# Bus_IO_and_Centronics_Card.net
KiCad netlist of a schematic drawn in EAGLE
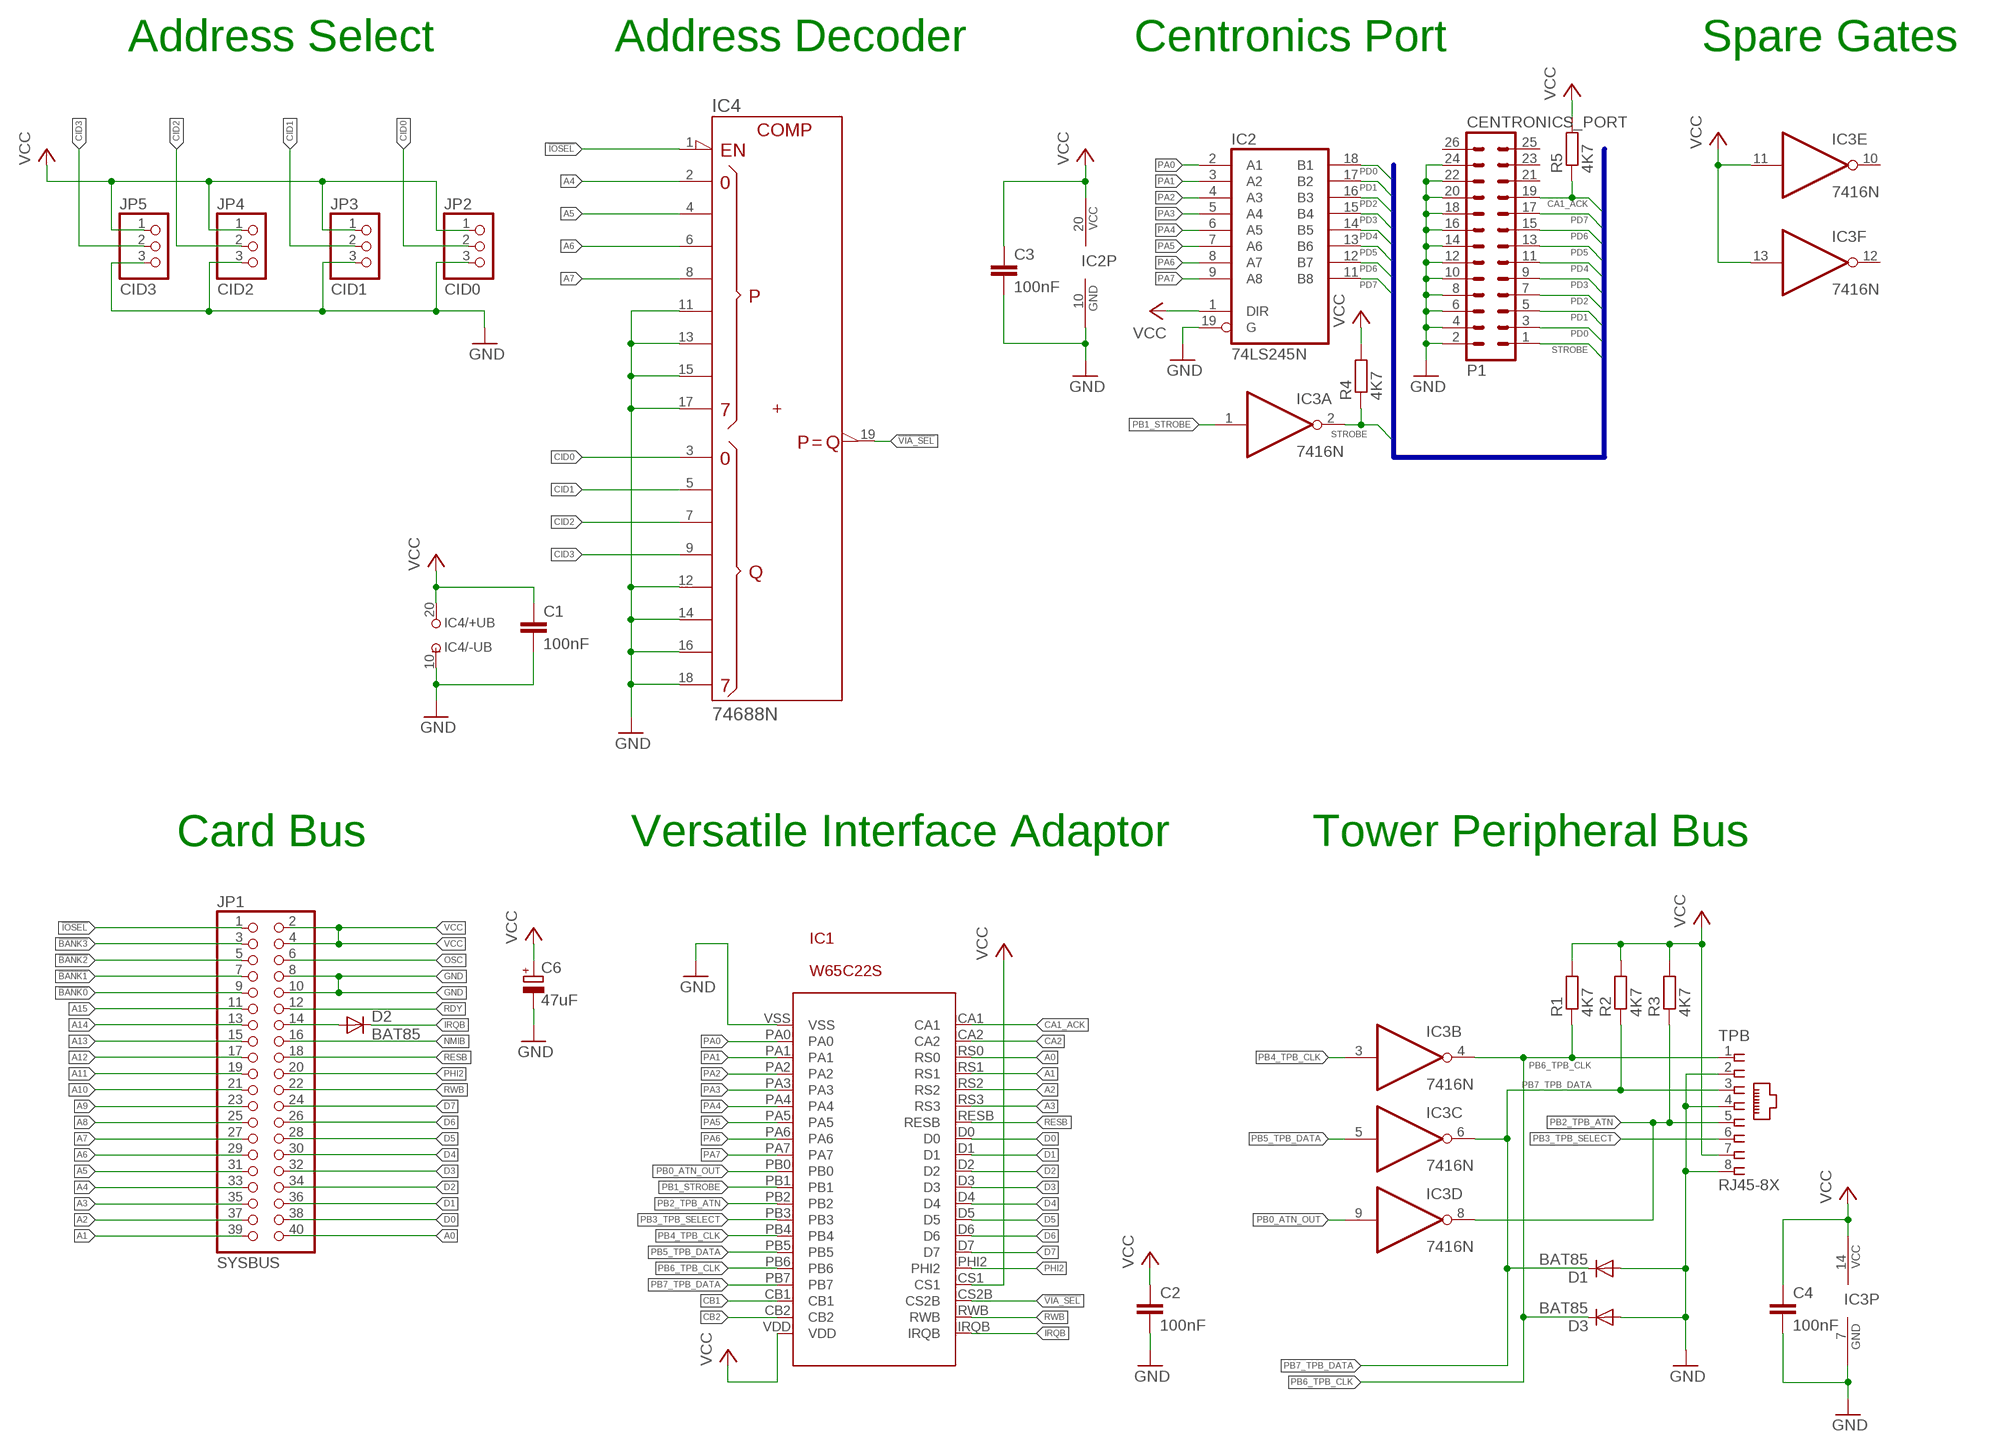
[diagram p0: schematic, sheet 1]

(export (version "E")
  (design (tool "Eeschema 10.0.6"))
  (components
    (comp (ref "C1")
      (value "100nF")
      (footprint "eagle-import:C050-025X075")
      (libsource (lib "eagle-import") (part "C-EU050-025X075"))
    )
    (comp (ref "C2")
      (value "100nF")
      (footprint "eagle-import:C050-025X075")
      (libsource (lib "eagle-import") (part "C-EU050-025X075"))
    )
    (comp (ref "C3")
      (value "100nF")
      (footprint "eagle-import:C050-025X075")
      (libsource (lib "eagle-import") (part "C-EU050-025X075"))
    )
    (comp (ref "C4")
      (value "100nF")
      (footprint "eagle-import:C050-025X075")
      (libsource (lib "eagle-import") (part "C-EU050-025X075"))
    )
    (comp (ref "C6")
      (value "47uF")
      (footprint "eagle-import:E2,5-7")
      (libsource (lib "eagle-import") (part "CPOL-EUE2.5-7"))
    )
    (comp (ref "CENTRONICS_PORT")
      (value "P1")
      (footprint "eagle-import:ML26L")
      (libsource (lib "eagle-import") (part "ML26L"))
    )
    (comp (ref "D1")
      (value "BAT85")
      (footprint "eagle-import:DO34-7")
      (libsource (lib "eagle-import") (part "BAT81"))
    )
    (comp (ref "D2")
      (value "BAT85")
      (footprint "eagle-import:DO34-7")
      (libsource (lib "eagle-import") (part "BAT81"))
    )
    (comp (ref "D3")
      (value "BAT85")
      (footprint "eagle-import:DO34-7")
      (libsource (lib "eagle-import") (part "BAT81"))
    )
    (comp (ref "IC1")
      (value "W65C22S")
      (footprint "eagle-import:W65C22-DIP")
      (libsource (lib "eagle-import") (part "W65C22"))
    )
    (comp (ref "IC2")
      (value "74LS245N")
      (footprint "eagle-import:DIL20")
      (libsource (lib "eagle-import") (part "74245NLS"))
    )
    (comp (ref "IC3")
      (value "7416N")
      (footprint "eagle-import:DIL14")
      (libsource (lib "eagle-import") (part "7416N"))
    )
    (comp (ref "IC4")
      (value "74688N")
      (footprint "eagle-import:DIL20")
      (libsource (lib "eagle-import") (part "74688N"))
    )
    (comp (ref "JP1")
      (value "SYSBUS")
      (footprint "eagle-import:2X20_90")
      (libsource (lib "eagle-import") (part "PINHD-2X20/90"))
    )
    (comp (ref "JP2")
      (value "CID0")
      (footprint "eagle-import:1X03")
      (libsource (lib "eagle-import") (part "PINHD-1X3"))
    )
    (comp (ref "JP3")
      (value "CID1")
      (footprint "eagle-import:1X03")
      (libsource (lib "eagle-import") (part "PINHD-1X3"))
    )
    (comp (ref "JP4")
      (value "CID2")
      (footprint "eagle-import:1X03")
      (libsource (lib "eagle-import") (part "PINHD-1X3"))
    )
    (comp (ref "JP5")
      (value "CID3")
      (footprint "eagle-import:1X03")
      (libsource (lib "eagle-import") (part "PINHD-1X3"))
    )
    (comp (ref "R1")
      (value "4K7")
      (footprint "eagle-import:0207_10")
      (libsource (lib "eagle-import") (part "R-EU_0207/10"))
    )
    (comp (ref "R2")
      (value "4K7")
      (footprint "eagle-import:0207_10")
      (libsource (lib "eagle-import") (part "R-EU_0207/10"))
    )
    (comp (ref "R3")
      (value "4K7")
      (footprint "eagle-import:0207_10")
      (libsource (lib "eagle-import") (part "R-EU_0207/10"))
    )
    (comp (ref "R4")
      (value "4K7")
      (footprint "eagle-import:0207_10")
      (libsource (lib "eagle-import") (part "R-EU_0207/10"))
    )
    (comp (ref "R5")
      (value "4K7")
      (footprint "eagle-import:0207_10")
      (libsource (lib "eagle-import") (part "R-EU_0207/10"))
    )
    (comp (ref "TPB")
      (value "RJ45-8X")
      (footprint "eagle-import:RJ45-NO-SHIELD")
      (libsource (lib "eagle-import") (part "RJ45-8X"))
    )
  )
  (nets
    (net (code "1") (name "/PD0") (class "Default")
      (node (ref "CENTRONICS_PORT") (pin "3") (pinfunction "3_3") (pintype "passive"))
      (node (ref "IC2") (pin "18") (pinfunction "B1_18") (pintype "bidirectional"))
    )
    (net (code "2") (name "/PD1") (class "Default")
      (node (ref "CENTRONICS_PORT") (pin "5") (pinfunction "5_5") (pintype "passive"))
      (node (ref "IC2") (pin "17") (pinfunction "B2_17") (pintype "bidirectional"))
    )
    (net (code "3") (name "/PD2") (class "Default")
      (node (ref "CENTRONICS_PORT") (pin "7") (pinfunction "7_7") (pintype "passive"))
      (node (ref "IC2") (pin "16") (pinfunction "B3_16") (pintype "bidirectional"))
    )
    (net (code "4") (name "/PD3") (class "Default")
      (node (ref "CENTRONICS_PORT") (pin "9") (pinfunction "9_9") (pintype "passive"))
      (node (ref "IC2") (pin "15") (pinfunction "B4_15") (pintype "bidirectional"))
    )
    (net (code "5") (name "/PD4") (class "Default")
      (node (ref "CENTRONICS_PORT") (pin "11") (pinfunction "11_11") (pintype "passive"))
      (node (ref "IC2") (pin "14") (pinfunction "B5_14") (pintype "bidirectional"))
    )
    (net (code "6") (name "/PD5") (class "Default")
      (node (ref "CENTRONICS_PORT") (pin "13") (pinfunction "13_13") (pintype "passive"))
      (node (ref "IC2") (pin "13") (pinfunction "B6_13") (pintype "bidirectional"))
    )
    (net (code "7") (name "/PD6") (class "Default")
      (node (ref "CENTRONICS_PORT") (pin "15") (pinfunction "15_15") (pintype "passive"))
      (node (ref "IC2") (pin "12") (pinfunction "B7_12") (pintype "bidirectional"))
    )
    (net (code "8") (name "/PD7") (class "Default")
      (node (ref "CENTRONICS_PORT") (pin "17") (pinfunction "17_17") (pintype "passive"))
      (node (ref "IC2") (pin "11") (pinfunction "B8_11") (pintype "bidirectional"))
    )
    (net (code "9") (name "/STROBE") (class "Default")
      (node (ref "CENTRONICS_PORT") (pin "1") (pinfunction "1_1") (pintype "passive"))
      (node (ref "IC3") (pin "2") (pinfunction "O_2") (pintype "open_collector"))
      (node (ref "R4") (pin "1") (pinfunction "1_1") (pintype "passive"))
    )
    (net (code "10") (name "/~{BANK0}") (class "Default")
      (node (ref "JP1") (pin "9") (pinfunction "9_9") (pintype "passive"))
    )
    (net (code "11") (name "/~{BANK1}") (class "Default")
      (node (ref "JP1") (pin "7") (pinfunction "7_7") (pintype "passive"))
    )
    (net (code "12") (name "/~{BANK2}") (class "Default")
      (node (ref "JP1") (pin "5") (pinfunction "5_5") (pintype "passive"))
    )
    (net (code "13") (name "/~{BANK3}") (class "Default")
      (node (ref "JP1") (pin "3") (pinfunction "3_3") (pintype "passive"))
    )
    (net (code "14") (name "/~{IOSEL}") (class "Default")
      (node (ref "IC4") (pin "1") (pinfunction "~{G}_1") (pintype "input"))
      (node (ref "JP1") (pin "1") (pinfunction "1_1") (pintype "passive"))
    )
    (net (code "15") (name "/~{VIA_SEL}") (class "Default")
      (node (ref "IC1") (pin "CS2B") (pinfunction "CS2B_CS2B") (pintype "bidirectional"))
      (node (ref "IC4") (pin "19") (pinfunction "~{P=Q}_19") (pintype "output"))
    )
    (net (code "16") (name "A0") (class "Default")
      (node (ref "IC1") (pin "RS0") (pinfunction "RS0_RS0") (pintype "input"))
      (node (ref "JP1") (pin "40") (pinfunction "40_40") (pintype "passive"))
    )
    (net (code "17") (name "A1") (class "Default")
      (node (ref "IC1") (pin "RS1") (pinfunction "RS1_RS1") (pintype "input"))
      (node (ref "JP1") (pin "39") (pinfunction "39_39") (pintype "passive"))
    )
    (net (code "18") (name "A2") (class "Default")
      (node (ref "IC1") (pin "RS2") (pinfunction "RS2_RS2") (pintype "input"))
      (node (ref "JP1") (pin "37") (pinfunction "37_37") (pintype "passive"))
    )
    (net (code "19") (name "A3") (class "Default")
      (node (ref "IC1") (pin "RS3") (pinfunction "RS3_RS3") (pintype "input"))
      (node (ref "JP1") (pin "35") (pinfunction "35_35") (pintype "passive"))
    )
    (net (code "20") (name "A4") (class "Default")
      (node (ref "IC4") (pin "2") (pinfunction "P0_2") (pintype "input"))
      (node (ref "JP1") (pin "33") (pinfunction "33_33") (pintype "passive"))
    )
    (net (code "21") (name "A5") (class "Default")
      (node (ref "IC4") (pin "4") (pinfunction "P1_4") (pintype "input"))
      (node (ref "JP1") (pin "31") (pinfunction "31_31") (pintype "passive"))
    )
    (net (code "22") (name "A6") (class "Default")
      (node (ref "IC4") (pin "6") (pinfunction "P2_6") (pintype "input"))
      (node (ref "JP1") (pin "29") (pinfunction "29_29") (pintype "passive"))
    )
    (net (code "23") (name "A7") (class "Default")
      (node (ref "IC4") (pin "8") (pinfunction "P3_8") (pintype "input"))
      (node (ref "JP1") (pin "27") (pinfunction "27_27") (pintype "passive"))
    )
    (net (code "24") (name "A8") (class "Default")
      (node (ref "JP1") (pin "25") (pinfunction "25_25") (pintype "passive"))
    )
    (net (code "25") (name "A9") (class "Default")
      (node (ref "JP1") (pin "23") (pinfunction "23_23") (pintype "passive"))
    )
    (net (code "26") (name "A10") (class "Default")
      (node (ref "JP1") (pin "21") (pinfunction "21_21") (pintype "passive"))
    )
    (net (code "27") (name "A11") (class "Default")
      (node (ref "JP1") (pin "19") (pinfunction "19_19") (pintype "passive"))
    )
    (net (code "28") (name "A12") (class "Default")
      (node (ref "JP1") (pin "17") (pinfunction "17_17") (pintype "passive"))
    )
    (net (code "29") (name "A13") (class "Default")
      (node (ref "JP1") (pin "15") (pinfunction "15_15") (pintype "passive"))
    )
    (net (code "30") (name "A14") (class "Default")
      (node (ref "JP1") (pin "13") (pinfunction "13_13") (pintype "passive"))
    )
    (net (code "31") (name "A15") (class "Default")
      (node (ref "JP1") (pin "11") (pinfunction "11_11") (pintype "passive"))
    )
    (net (code "32") (name "CA1_ACK") (class "Default")
      (node (ref "CENTRONICS_PORT") (pin "19") (pinfunction "19_19") (pintype "passive"))
      (node (ref "IC1") (pin "CA1") (pinfunction "CA1_CA1") (pintype "bidirectional"))
      (node (ref "R5") (pin "1") (pinfunction "1_1") (pintype "passive"))
    )
    (net (code "33") (name "CA2") (class "Default")
      (node (ref "IC1") (pin "CA2") (pinfunction "CA2_CA2") (pintype "bidirectional"))
    )
    (net (code "34") (name "CB1") (class "Default")
      (node (ref "IC1") (pin "CB1") (pinfunction "CB1_CB1") (pintype "bidirectional"))
    )
    (net (code "35") (name "CB2") (class "Default")
      (node (ref "IC1") (pin "CB2") (pinfunction "CB2_CB2") (pintype "bidirectional"))
    )
    (net (code "36") (name "CID0") (class "Default")
      (node (ref "IC4") (pin "3") (pinfunction "Q0_3") (pintype "input"))
      (node (ref "JP2") (pin "2") (pinfunction "2_2") (pintype "passive"))
    )
    (net (code "37") (name "CID1") (class "Default")
      (node (ref "IC4") (pin "5") (pinfunction "Q1_5") (pintype "input"))
      (node (ref "JP3") (pin "2") (pinfunction "2_2") (pintype "passive"))
    )
    (net (code "38") (name "CID2") (class "Default")
      (node (ref "IC4") (pin "7") (pinfunction "Q2_7") (pintype "input"))
      (node (ref "JP4") (pin "2") (pinfunction "2_2") (pintype "passive"))
    )
    (net (code "39") (name "CID3") (class "Default")
      (node (ref "IC4") (pin "9") (pinfunction "Q3_9") (pintype "input"))
      (node (ref "JP5") (pin "2") (pinfunction "2_2") (pintype "passive"))
    )
    (net (code "40") (name "D0") (class "Default")
      (node (ref "IC1") (pin "D0") (pinfunction "D0_D0") (pintype "bidirectional"))
      (node (ref "JP1") (pin "38") (pinfunction "38_38") (pintype "passive"))
    )
    (net (code "41") (name "D1") (class "Default")
      (node (ref "IC1") (pin "D1") (pinfunction "D1_D1") (pintype "bidirectional"))
      (node (ref "JP1") (pin "36") (pinfunction "36_36") (pintype "passive"))
    )
    (net (code "42") (name "D2") (class "Default")
      (node (ref "IC1") (pin "D2") (pinfunction "D2_D2") (pintype "bidirectional"))
      (node (ref "JP1") (pin "34") (pinfunction "34_34") (pintype "passive"))
    )
    (net (code "43") (name "D3") (class "Default")
      (node (ref "IC1") (pin "D3") (pinfunction "D3_D3") (pintype "bidirectional"))
      (node (ref "JP1") (pin "32") (pinfunction "32_32") (pintype "passive"))
    )
    (net (code "44") (name "D4") (class "Default")
      (node (ref "IC1") (pin "D4") (pinfunction "D4_D4") (pintype "bidirectional"))
      (node (ref "JP1") (pin "30") (pinfunction "30_30") (pintype "passive"))
    )
    (net (code "45") (name "D5") (class "Default")
      (node (ref "IC1") (pin "D5") (pinfunction "D5_D5") (pintype "bidirectional"))
      (node (ref "JP1") (pin "28") (pinfunction "28_28") (pintype "passive"))
    )
    (net (code "46") (name "D6") (class "Default")
      (node (ref "IC1") (pin "D6") (pinfunction "D6_D6") (pintype "bidirectional"))
      (node (ref "JP1") (pin "26") (pinfunction "26_26") (pintype "passive"))
    )
    (net (code "47") (name "D7") (class "Default")
      (node (ref "IC1") (pin "D7") (pinfunction "D7_D7") (pintype "bidirectional"))
      (node (ref "JP1") (pin "24") (pinfunction "24_24") (pintype "passive"))
    )
    (net (code "48") (name "GND") (class "Default")
      (node (ref "C1") (pin "2") (pinfunction "2_2") (pintype "passive"))
      (node (ref "C2") (pin "2") (pinfunction "2_2") (pintype "passive"))
      (node (ref "C3") (pin "2") (pinfunction "2_2") (pintype "passive"))
      (node (ref "C4") (pin "2") (pinfunction "2_2") (pintype "passive"))
      (node (ref "C6") (pin "-") (pinfunction "-_-") (pintype "passive"))
      (node (ref "CENTRONICS_PORT") (pin "10") (pinfunction "10_10") (pintype "passive"))
      (node (ref "CENTRONICS_PORT") (pin "12") (pinfunction "12_12") (pintype "passive"))
      (node (ref "CENTRONICS_PORT") (pin "14") (pinfunction "14_14") (pintype "passive"))
      (node (ref "CENTRONICS_PORT") (pin "16") (pinfunction "16_16") (pintype "passive"))
      (node (ref "CENTRONICS_PORT") (pin "18") (pinfunction "18_18") (pintype "passive"))
      (node (ref "CENTRONICS_PORT") (pin "2") (pinfunction "2_2") (pintype "passive"))
      (node (ref "CENTRONICS_PORT") (pin "20") (pinfunction "20_20") (pintype "passive"))
      (node (ref "CENTRONICS_PORT") (pin "22") (pinfunction "22_22") (pintype "passive"))
      (node (ref "CENTRONICS_PORT") (pin "24") (pinfunction "24_24") (pintype "passive"))
      (node (ref "CENTRONICS_PORT") (pin "4") (pinfunction "4_4") (pintype "passive"))
      (node (ref "CENTRONICS_PORT") (pin "6") (pinfunction "6_6") (pintype "passive"))
      (node (ref "CENTRONICS_PORT") (pin "8") (pinfunction "8_8") (pintype "passive"))
      (node (ref "D1") (pin "A") (pinfunction "A_A") (pintype "passive"))
      (node (ref "D3") (pin "A") (pinfunction "A_A") (pintype "passive"))
      (node (ref "IC1") (pin "VSS") (pinfunction "VSS_VSS") (pintype "power_in"))
      (node (ref "IC2") (pin "10") (pinfunction "GND_10") (pintype "power_in"))
      (node (ref "IC2") (pin "19") (pinfunction "G_19") (pintype "input"))
      (node (ref "IC3") (pin "7") (pinfunction "GND_7") (pintype "power_in"))
      (node (ref "IC4") (pin "10") (pinfunction "-UB_10") (pintype "power_in"))
      (node (ref "IC4") (pin "11") (pinfunction "P4_11") (pintype "input"))
      (node (ref "IC4") (pin "12") (pinfunction "Q4_12") (pintype "input"))
      (node (ref "IC4") (pin "13") (pinfunction "P5_13") (pintype "input"))
      (node (ref "IC4") (pin "14") (pinfunction "Q5_14") (pintype "input"))
      (node (ref "IC4") (pin "15") (pinfunction "P6_15") (pintype "input"))
      (node (ref "IC4") (pin "16") (pinfunction "Q6_16") (pintype "input"))
      (node (ref "IC4") (pin "17") (pinfunction "P7_17") (pintype "input"))
      (node (ref "IC4") (pin "18") (pinfunction "Q7_18") (pintype "input"))
      (node (ref "JP1") (pin "10") (pinfunction "10_10") (pintype "passive"))
      (node (ref "JP1") (pin "8") (pinfunction "8_8") (pintype "passive"))
      (node (ref "JP2") (pin "3") (pinfunction "3_3") (pintype "passive"))
      (node (ref "JP3") (pin "3") (pinfunction "3_3") (pintype "passive"))
      (node (ref "JP4") (pin "3") (pinfunction "3_3") (pintype "passive"))
      (node (ref "JP5") (pin "3") (pinfunction "3_3") (pintype "passive"))
      (node (ref "TPB") (pin "2") (pinfunction "2_2") (pintype "passive"))
      (node (ref "TPB") (pin "4") (pinfunction "4_4") (pintype "passive"))
      (node (ref "TPB") (pin "8") (pinfunction "8_8") (pintype "passive"))
    )
    (net (code "49") (name "IRQB") (class "Default")
      (node (ref "D2") (pin "C") (pinfunction "C_C") (pintype "passive"))
      (node (ref "IC1") (pin "IRQB") (pinfunction "IRQB_IRQB") (pintype "output"))
    )
    (net (code "50") (name "NMIB") (class "Default")
      (node (ref "JP1") (pin "16") (pinfunction "16_16") (pintype "passive"))
    )
    (net (code "51") (name "Net-(D2-PadA)") (class "Default")
      (node (ref "D2") (pin "A") (pinfunction "A_A") (pintype "passive"))
      (node (ref "JP1") (pin "14") (pinfunction "14_14") (pintype "passive"))
    )
    (net (code "52") (name "OSC") (class "Default")
      (node (ref "JP1") (pin "6") (pinfunction "6_6") (pintype "passive"))
    )
    (net (code "53") (name "PA0") (class "Default")
      (node (ref "IC1") (pin "PA0") (pinfunction "PA0_PA0") (pintype "bidirectional"))
      (node (ref "IC2") (pin "2") (pinfunction "A1_2") (pintype "bidirectional"))
    )
    (net (code "54") (name "PA1") (class "Default")
      (node (ref "IC1") (pin "PA1") (pinfunction "PA1_PA1") (pintype "bidirectional"))
      (node (ref "IC2") (pin "3") (pinfunction "A2_3") (pintype "bidirectional"))
    )
    (net (code "55") (name "PA2") (class "Default")
      (node (ref "IC1") (pin "PA2") (pinfunction "PA2_PA2") (pintype "bidirectional"))
      (node (ref "IC2") (pin "4") (pinfunction "A3_4") (pintype "bidirectional"))
    )
    (net (code "56") (name "PA3") (class "Default")
      (node (ref "IC1") (pin "PA3") (pinfunction "PA3_PA3") (pintype "bidirectional"))
      (node (ref "IC2") (pin "5") (pinfunction "A4_5") (pintype "bidirectional"))
    )
    (net (code "57") (name "PA4") (class "Default")
      (node (ref "IC1") (pin "PA4") (pinfunction "PA4_PA4") (pintype "bidirectional"))
      (node (ref "IC2") (pin "6") (pinfunction "A5_6") (pintype "bidirectional"))
    )
    (net (code "58") (name "PA5") (class "Default")
      (node (ref "IC1") (pin "PA5") (pinfunction "PA5_PA5") (pintype "bidirectional"))
      (node (ref "IC2") (pin "7") (pinfunction "A6_7") (pintype "bidirectional"))
    )
    (net (code "59") (name "PA6") (class "Default")
      (node (ref "IC1") (pin "PA6") (pinfunction "PA6_PA6") (pintype "bidirectional"))
      (node (ref "IC2") (pin "8") (pinfunction "A7_8") (pintype "bidirectional"))
    )
    (net (code "60") (name "PA7") (class "Default")
      (node (ref "IC1") (pin "PA7") (pinfunction "PA7_PA7") (pintype "bidirectional"))
      (node (ref "IC2") (pin "9") (pinfunction "A8_9") (pintype "bidirectional"))
    )
    (net (code "61") (name "PB0_ATN_OUT") (class "Default")
      (node (ref "IC1") (pin "PB0") (pinfunction "PB0_PB0") (pintype "bidirectional"))
      (node (ref "IC3") (pin "9") (pinfunction "I_9") (pintype "input"))
    )
    (net (code "62") (name "PB1_STROBE") (class "Default")
      (node (ref "IC1") (pin "PB1") (pinfunction "PB1_PB1") (pintype "bidirectional"))
      (node (ref "IC3") (pin "1") (pinfunction "I_1") (pintype "input"))
    )
    (net (code "63") (name "PB2_TPB_ATN") (class "Default")
      (node (ref "IC1") (pin "PB2") (pinfunction "PB2_PB2") (pintype "bidirectional"))
      (node (ref "IC3") (pin "8") (pinfunction "O_8") (pintype "open_collector"))
      (node (ref "R3") (pin "1") (pinfunction "1_1") (pintype "passive"))
      (node (ref "TPB") (pin "5") (pinfunction "5_5") (pintype "passive"))
    )
    (net (code "64") (name "PB3_TPB_SELECT") (class "Default")
      (node (ref "IC1") (pin "PB3") (pinfunction "PB3_PB3") (pintype "bidirectional"))
      (node (ref "TPB") (pin "6") (pinfunction "6_6") (pintype "passive"))
    )
    (net (code "65") (name "PB4_TPB_CLK") (class "Default")
      (node (ref "IC1") (pin "PB4") (pinfunction "PB4_PB4") (pintype "bidirectional"))
      (node (ref "IC3") (pin "3") (pinfunction "I_3") (pintype "input"))
    )
    (net (code "66") (name "PB5_TPB_DATA") (class "Default")
      (node (ref "IC1") (pin "PB5") (pinfunction "PB5_PB5") (pintype "bidirectional"))
      (node (ref "IC3") (pin "5") (pinfunction "I_5") (pintype "input"))
    )
    (net (code "67") (name "PB6_TPB_CLK") (class "Default")
      (node (ref "D3") (pin "C") (pinfunction "C_C") (pintype "passive"))
      (node (ref "IC1") (pin "PB6") (pinfunction "PB6_PB6") (pintype "bidirectional"))
      (node (ref "IC3") (pin "4") (pinfunction "O_4") (pintype "open_collector"))
      (node (ref "R1") (pin "1") (pinfunction "1_1") (pintype "passive"))
      (node (ref "TPB") (pin "1") (pinfunction "1_1") (pintype "passive"))
    )
    (net (code "68") (name "PB7_TPB_DATA") (class "Default")
      (node (ref "D1") (pin "C") (pinfunction "C_C") (pintype "passive"))
      (node (ref "IC1") (pin "PB7") (pinfunction "PB7_PB7") (pintype "bidirectional"))
      (node (ref "IC3") (pin "6") (pinfunction "O_6") (pintype "open_collector"))
      (node (ref "R2") (pin "1") (pinfunction "1_1") (pintype "passive"))
      (node (ref "TPB") (pin "3") (pinfunction "3_3") (pintype "passive"))
    )
    (net (code "69") (name "PHI2") (class "Default")
      (node (ref "IC1") (pin "PHI2") (pinfunction "PHI2_PHI2") (pintype "input"))
      (node (ref "JP1") (pin "20") (pinfunction "20_20") (pintype "passive"))
    )
    (net (code "70") (name "RDY") (class "Default")
      (node (ref "JP1") (pin "12") (pinfunction "12_12") (pintype "passive"))
    )
    (net (code "71") (name "RESB") (class "Default")
      (node (ref "IC1") (pin "RESB") (pinfunction "RESB_RESB") (pintype "input"))
      (node (ref "JP1") (pin "18") (pinfunction "18_18") (pintype "passive"))
    )
    (net (code "72") (name "RWB") (class "Default")
      (node (ref "IC1") (pin "RWB") (pinfunction "RWB_RWB") (pintype "input"))
      (node (ref "JP1") (pin "22") (pinfunction "22_22") (pintype "passive"))
    )
    (net (code "73") (name "VCC") (class "Default")
      (node (ref "C1") (pin "1") (pinfunction "1_1") (pintype "passive"))
      (node (ref "C2") (pin "1") (pinfunction "1_1") (pintype "passive"))
      (node (ref "C3") (pin "1") (pinfunction "1_1") (pintype "passive"))
      (node (ref "C4") (pin "1") (pinfunction "1_1") (pintype "passive"))
      (node (ref "C6") (pin "+") (pinfunction "+_+") (pintype "passive"))
      (node (ref "IC1") (pin "CS1") (pinfunction "CS1_CS1") (pintype "bidirectional"))
      (node (ref "IC1") (pin "VDD") (pinfunction "VDD_VDD") (pintype "power_in"))
      (node (ref "IC2") (pin "1") (pinfunction "DIR_1") (pintype "input"))
      (node (ref "IC2") (pin "20") (pinfunction "VCC_20") (pintype "power_in"))
      (node (ref "IC3") (pin "11") (pinfunction "I_11") (pintype "input"))
      (node (ref "IC3") (pin "13") (pinfunction "I_13") (pintype "input"))
      (node (ref "IC3") (pin "14") (pinfunction "VCC_14") (pintype "power_in"))
      (node (ref "IC4") (pin "20") (pinfunction "+UB_20") (pintype "power_in"))
      (node (ref "JP1") (pin "2") (pinfunction "2_2") (pintype "passive"))
      (node (ref "JP1") (pin "4") (pinfunction "4_4") (pintype "passive"))
      (node (ref "JP2") (pin "1") (pinfunction "1_1") (pintype "passive"))
      (node (ref "JP3") (pin "1") (pinfunction "1_1") (pintype "passive"))
      (node (ref "JP4") (pin "1") (pinfunction "1_1") (pintype "passive"))
      (node (ref "JP5") (pin "1") (pinfunction "1_1") (pintype "passive"))
      (node (ref "R1") (pin "2") (pinfunction "2_2") (pintype "passive"))
      (node (ref "R2") (pin "2") (pinfunction "2_2") (pintype "passive"))
      (node (ref "R3") (pin "2") (pinfunction "2_2") (pintype "passive"))
      (node (ref "R4") (pin "2") (pinfunction "2_2") (pintype "passive"))
      (node (ref "R5") (pin "2") (pinfunction "2_2") (pintype "passive"))
      (node (ref "TPB") (pin "7") (pinfunction "7_7") (pintype "passive"))
    )
    (net (code "74") (name "unconnected-(CENTRONICS_PORT-Pad21)") (class "Default")
      (node (ref "CENTRONICS_PORT") (pin "21") (pinfunction "21_21") (pintype "passive"))
    )
    (net (code "75") (name "unconnected-(CENTRONICS_PORT-Pad23)") (class "Default")
      (node (ref "CENTRONICS_PORT") (pin "23") (pinfunction "23_23") (pintype "passive"))
    )
    (net (code "76") (name "unconnected-(CENTRONICS_PORT-Pad25)") (class "Default")
      (node (ref "CENTRONICS_PORT") (pin "25") (pinfunction "25_25") (pintype "passive"))
    )
    (net (code "77") (name "unconnected-(CENTRONICS_PORT-Pad26)") (class "Default")
      (node (ref "CENTRONICS_PORT") (pin "26") (pinfunction "26_26") (pintype "passive"))
    )
    (net (code "78") (name "unconnected-(IC3E-O-Pad10)") (class "Default")
      (node (ref "IC3") (pin "10") (pinfunction "O_10") (pintype "open_collector"))
    )
    (net (code "79") (name "unconnected-(IC3F-O-Pad12)") (class "Default")
      (node (ref "IC3") (pin "12") (pinfunction "O_12") (pintype "open_collector"))
    )
  )
)
